# 00_Main.net
KiCad netlist of a schematic drawn in Altium Designer
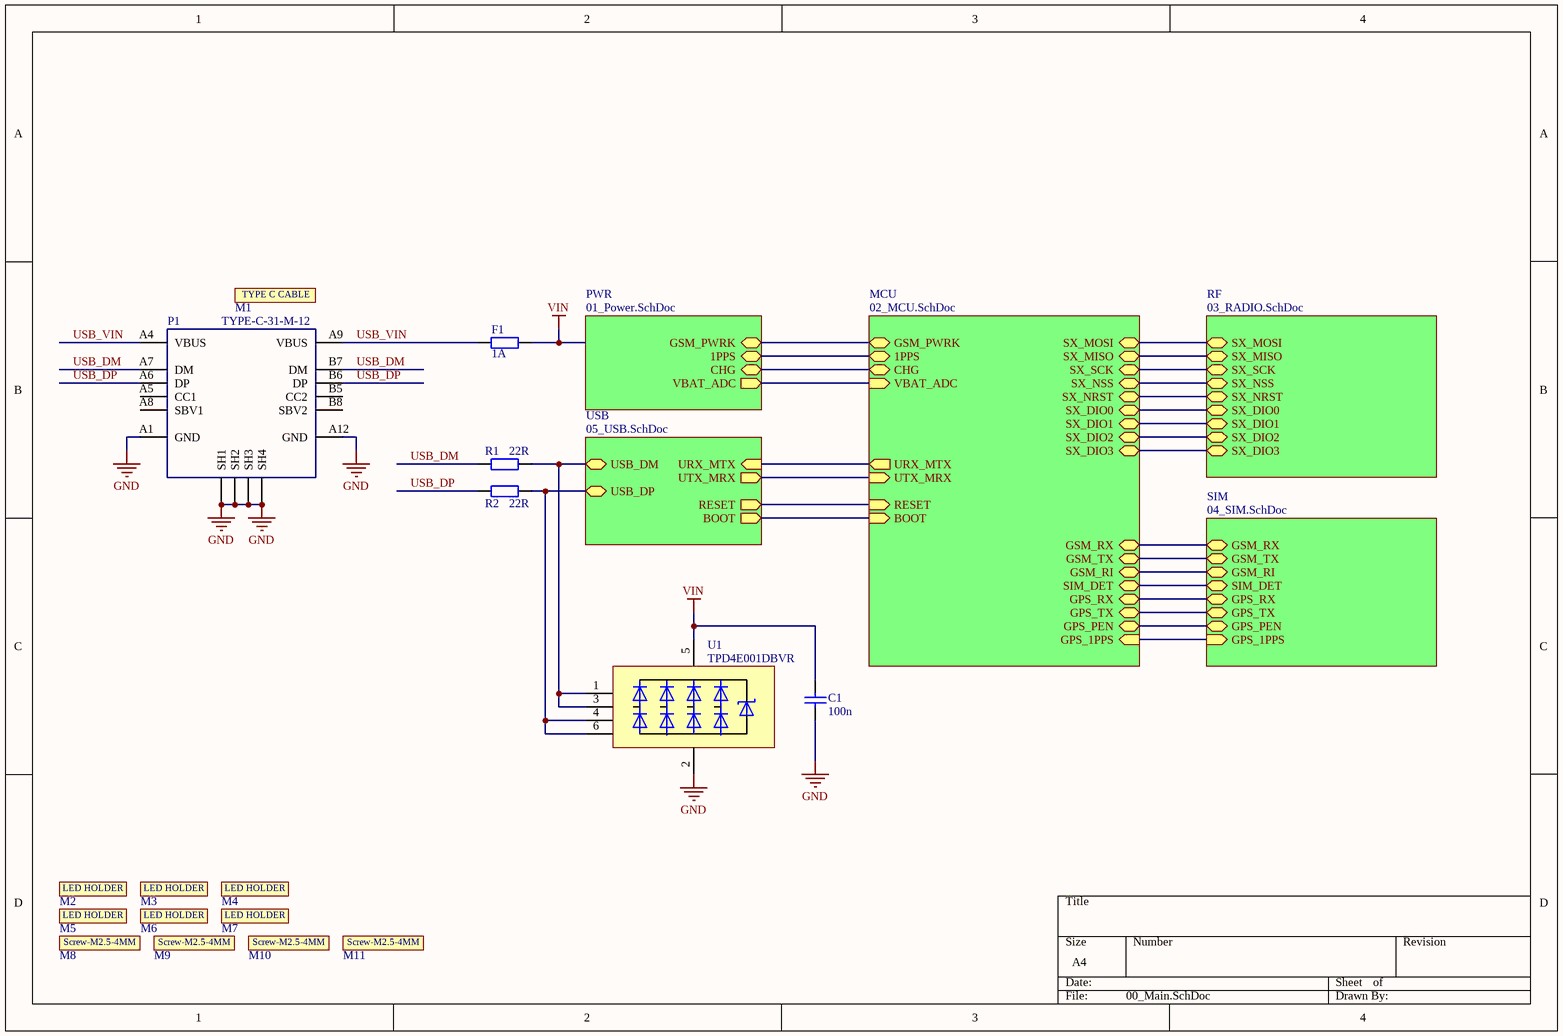
[diagram p0: 00_Main.SchDoc]

(export (version "E")
  (design (tool "Eeschema 10.0.6"))
  (components
    (comp (ref "C1")
      (value "100n")
      (footprint "C0603_IPC_MD")
      (description "CAP CER 0.1UF 16V X7R 0603")
      (fields
        (field (name "MANUFACTURER") "Samsung Electro-Mechanics")
        (field (name "MANUFACTURER PART NUMBER") "CL10B104KO8NNNC")
      )
      (libsource (lib "alfasat_lib") (part "CL10B104KO8NNNC"))
    )
    (comp (ref "F1")
      (value "1A")
      (footprint "R0603_IPC_MD")
      (description "FUSE BOARD MOUNT 1A 32VDC 0603")
      (fields
        (field (name "MANUFACTURER") "Bourns Inc.")
        (field (name "MANUFACTURER PART NUMBER") "MFU0603FF01000P500")
      )
      (libsource (lib "alfasat_lib") (part "MFU0603FF01000P500"))
    )
    (comp (ref "M1")
      (value "UGREEN-PVC-TYPE-C")
      (description "Ugreen USB Type C Cable")
      (fields (field (name "MANUFACTURER") "China"))
      (libsource (lib "alfasat_lib") (part "TYPE-C-CABLE"))
    )
    (comp (ref "M2")
      (value "LedHolderM3")
      (description "LED-HOLDER-M3")
      (fields (field (name "MANUFACTURER") "China"))
      (libsource (lib "alfasat_lib") (part "LED-HOLDER-M3"))
    )
    (comp (ref "M3")
      (value "LedHolderM3")
      (description "LED-HOLDER-M3")
      (fields (field (name "MANUFACTURER") "China"))
      (libsource (lib "alfasat_lib") (part "LED-HOLDER-M3"))
    )
    (comp (ref "M4")
      (value "LedHolderM3")
      (description "LED-HOLDER-M3")
      (fields (field (name "MANUFACTURER") "China"))
      (libsource (lib "alfasat_lib") (part "LED-HOLDER-M3"))
    )
    (comp (ref "M5")
      (value "C94096")
      (footprint "LED3MM_HOLDER")
      (description "LED Light Pipes 4*10 RoHS")
      (fields (field (name "MANUFACTURER") "HIWA"))
      (libsource (lib "alfasat_lib") (part "C94096"))
    )
    (comp (ref "M6")
      (value "C94096")
      (footprint "LED3MM_HOLDER")
      (description "LED Light Pipes 4*10 RoHS")
      (fields (field (name "MANUFACTURER") "HIWA"))
      (libsource (lib "alfasat_lib") (part "C94096"))
    )
    (comp (ref "M7")
      (value "C94096")
      (footprint "LED3MM_HOLDER")
      (description "LED Light Pipes 4*10 RoHS")
      (fields (field (name "MANUFACTURER") "HIWA"))
      (libsource (lib "alfasat_lib") (part "C94096"))
    )
    (comp (ref "M8")
      (value "ScrewST-M3-6MM")
      (fields (field (name "MANUFACTURER") "China"))
      (libsource (lib "alfasat_lib") (part "ScrewST-M3-6MM"))
    )
    (comp (ref "M9")
      (value "ScrewST-M3-6MM")
      (fields (field (name "MANUFACTURER") "China"))
      (libsource (lib "alfasat_lib") (part "ScrewST-M3-6MM"))
    )
    (comp (ref "M10")
      (value "ScrewST-M3-6MM")
      (fields (field (name "MANUFACTURER") "China"))
      (libsource (lib "alfasat_lib") (part "ScrewST-M3-6MM"))
    )
    (comp (ref "M11")
      (value "ScrewST-M3-6MM")
      (fields (field (name "MANUFACTURER") "China"))
      (libsource (lib "alfasat_lib") (part "ScrewST-M3-6MM"))
    )
    (comp (ref "P1")
      (value "TYPE-C-31-M-12")
      (footprint "TYPE-C-C165948")
      (description "TYPE C PCB TH CONN")
      (fields (field (name "MANUFACTURER") "Korean Hroparts Elec"))
      (libsource (lib "alfasat_lib") (part "TYPE-C-31-M-12"))
    )
    (comp (ref "R1")
      (value "22R")
      (footprint "R0603_IPC_MD")
      (description "RES SMD 22 OHM 5% 1/10W 0603")
      (fields
        (field (name "MANUFACTURER") "Bourns Inc.")
        (field (name "MANUFACTURER PART NUMBER") "CR0603-JW-220ELF")
      )
      (libsource (lib "alfasat_lib") (part "CR0603-JW-220ELF"))
    )
    (comp (ref "R2")
      (value "22R")
      (footprint "R0603_IPC_MD")
      (description "RES SMD 22 OHM 5% 1/10W 0603")
      (fields
        (field (name "MANUFACTURER") "Bourns Inc.")
        (field (name "MANUFACTURER PART NUMBER") "CR0603-JW-220ELF")
      )
      (libsource (lib "") (part "CR0603-JW-220ELF_1"))
    )
    (comp (ref "U1")
      (value "TPD4E001DBVR")
      (footprint "SOT23-6")
      (description "4x TVS DIODE 5.5V SOT23-6")
      (fields (field (name "MANUFACTURER") "TI"))
      (libsource (lib "alfasat_lib") (part "TPD4E001DBVR"))
    )
  )
  (nets
    (net (code "24") (name "/USB_DM") (class "Default")
      (node (ref "P1") (pin "A7") (pinfunction "DM_A7") (pintype "passive"))
      (node (ref "P1") (pin "B7") (pinfunction "DM_B7") (pintype "passive"))
      (node (ref "R1") (pin "1") (pinfunction "1_1") (pintype "passive"))
    )
    (net (code "25") (name "/USB_DM_1") (class "Default")
      (node (ref "R1") (pin "2") (pinfunction "2_2") (pintype "passive"))
      (node (ref "U1") (pin "1") (pinfunction "IO1_1") (pintype "passive"))
      (node (ref "U1") (pin "3") (pinfunction "IO2_3") (pintype "passive"))
    )
    (net (code "26") (name "/USB_DP") (class "Default")
      (node (ref "P1") (pin "A6") (pinfunction "DP_A6") (pintype "passive"))
      (node (ref "P1") (pin "B6") (pinfunction "DP_B6") (pintype "passive"))
      (node (ref "R2") (pin "1") (pinfunction "1_1") (pintype "passive"))
    )
    (net (code "27") (name "/USB_DP_1") (class "Default")
      (node (ref "R2") (pin "2") (pinfunction "2_2") (pintype "passive"))
      (node (ref "U1") (pin "4") (pinfunction "IO3_4") (pintype "passive"))
      (node (ref "U1") (pin "6") (pinfunction "IO4_6") (pintype "passive"))
    )
    (net (code "28") (name "/USB_VIN") (class "Default")
      (node (ref "F1") (pin "1") (pinfunction "1_1") (pintype "passive"))
      (node (ref "P1") (pin "A4") (pinfunction "VBUS_A4") (pintype "passive"))
      (node (ref "P1") (pin "A9") (pinfunction "VBUS_A9") (pintype "passive"))
    )
    (net (code "31") (name "GND") (class "Default")
      (node (ref "C1") (pin "2") (pinfunction "2_2") (pintype "passive"))
      (node (ref "P1") (pin "A1") (pinfunction "GND_A1") (pintype "passive"))
      (node (ref "P1") (pin "A12") (pinfunction "GND_A12") (pintype "passive"))
      (node (ref "P1") (pin "SH1") (pinfunction "SH1_SH1") (pintype "passive"))
      (node (ref "P1") (pin "SH2") (pinfunction "SH2_SH2") (pintype "passive"))
      (node (ref "P1") (pin "SH3") (pinfunction "SH3_SH3") (pintype "passive"))
      (node (ref "P1") (pin "SH4") (pinfunction "SH4_SH4") (pintype "passive"))
      (node (ref "U1") (pin "2") (pinfunction "GND_2") (pintype "power_in"))
    )
    (net (code "32") (name "VIN") (class "Default")
      (node (ref "C1") (pin "1") (pinfunction "1_1") (pintype "passive"))
      (node (ref "F1") (pin "2") (pinfunction "2_2") (pintype "passive"))
      (node (ref "U1") (pin "5") (pinfunction "VCC_5") (pintype "power_in"))
    )
    (net (code "33") (name "unconnected-(P1-CC1-PadA5)") (class "Default")
      (node (ref "P1") (pin "A5") (pinfunction "CC1_A5") (pintype "passive"))
    )
    (net (code "34") (name "unconnected-(P1-CC2-PadB5)") (class "Default")
      (node (ref "P1") (pin "B5") (pinfunction "CC2_B5") (pintype "passive"))
    )
    (net (code "35") (name "unconnected-(P1-SBV1-PadA8)") (class "Default")
      (node (ref "P1") (pin "A8") (pinfunction "SBV1_A8") (pintype "passive"))
    )
    (net (code "36") (name "unconnected-(P1-SBV2-PadB8)") (class "Default")
      (node (ref "P1") (pin "B8") (pinfunction "SBV2_B8") (pintype "passive"))
    )
  )
)
